# L298N_Motor_Driver.net
KiCad netlist of a schematic drawn in EasyEDA Pro
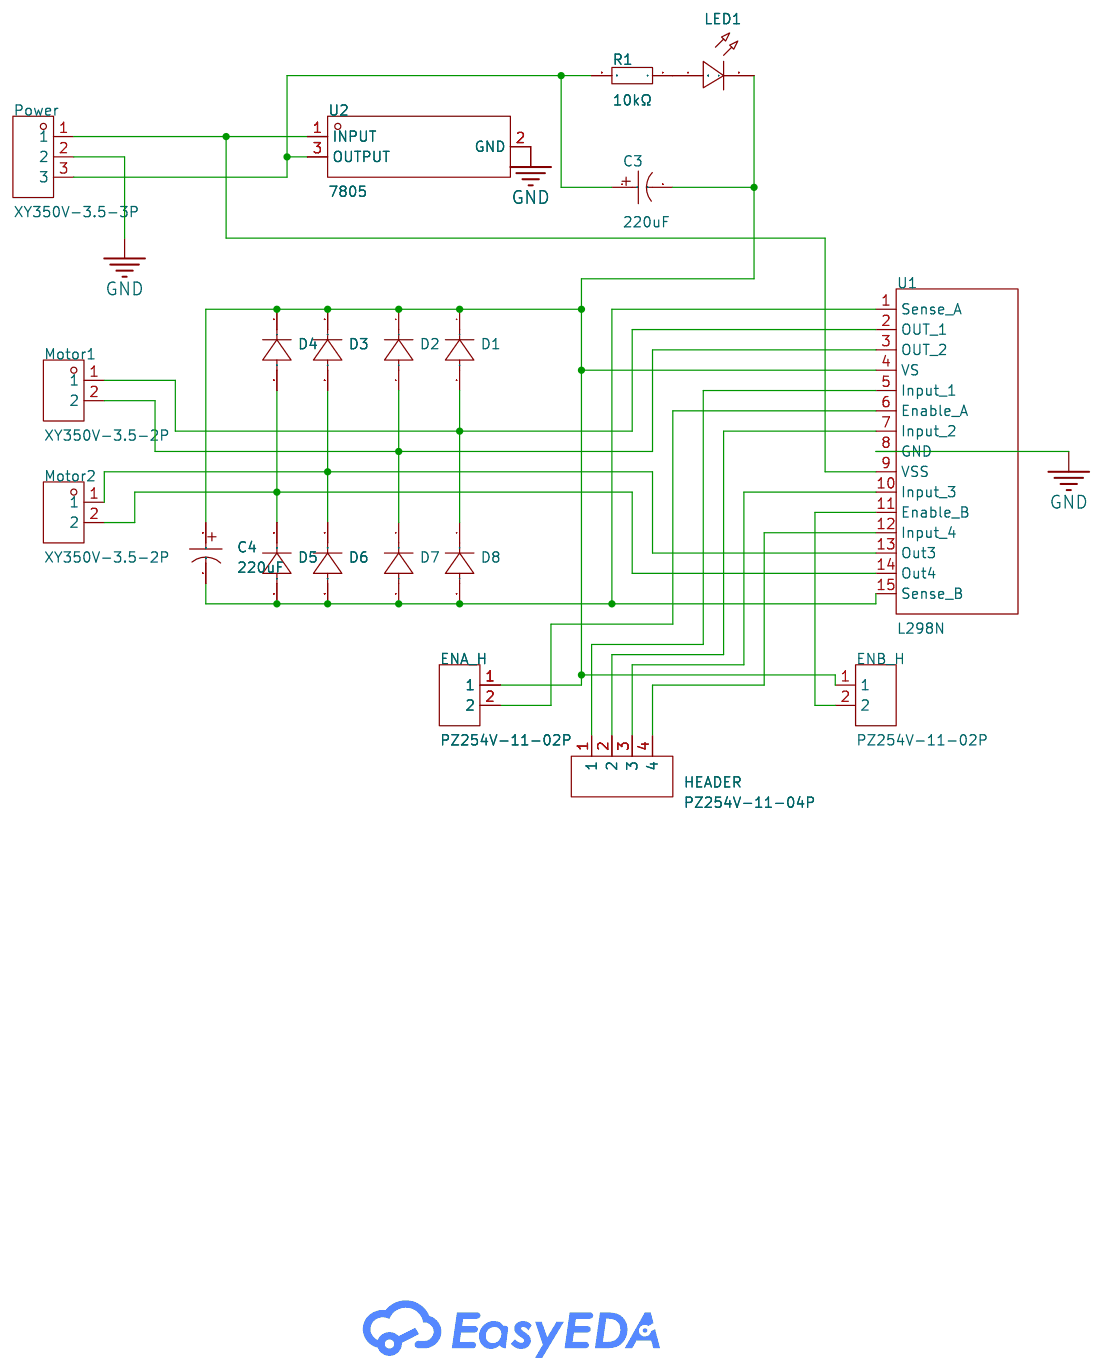
[diagram p0: schematic sheet]

(export (version "E")
  (design (tool "Eeschema 10.0.6"))
  (components
    (comp (ref "C3")
      (value "220uF")
      (footprint "easyedapro:CAP-SMD_BD8.0-L8.3-W8.3-FD")
      (fields (field (name "Manufacturer Part") "RVT1E221M0810") (field (name "Manufacturer") "Chengx(承兴)"))
      (libsource (lib "easyedapro") (part "UT1E221M0810VG"))
    )
    (comp (ref "C4")
      (value "220uF")
      (footprint "easyedapro:CAP-SMD_BD8.0-L8.3-W8.3-FD")
      (fields (field (name "Manufacturer Part") "RVT1E221M0810") (field (name "Manufacturer") "Chengx(承兴)"))
      (libsource (lib "easyedapro") (part "UT1E221M0810VG"))
    )
    (comp (ref "D1")
      (value "~")
      (footprint "easyedapro:DO-41_BD2.4-L4.7-P8.70-D0.9-RD")
      (libsource (lib "easyedapro") (part "D_1N4007"))
    )
    (comp (ref "D2")
      (value "~")
      (footprint "easyedapro:DO-41_BD2.4-L4.7-P8.70-D0.9-RD")
      (libsource (lib "easyedapro") (part "D_1N4007"))
    )
    (comp (ref "D3")
      (value "~")
      (footprint "easyedapro:DO-41_BD2.4-L4.7-P8.70-D0.9-RD")
      (libsource (lib "easyedapro") (part "D_1N4007"))
    )
    (comp (ref "D4")
      (value "~")
      (footprint "easyedapro:DO-41_BD2.4-L4.7-P8.70-D0.9-RD")
      (libsource (lib "easyedapro") (part "D_1N4007"))
    )
    (comp (ref "D5")
      (value "~")
      (footprint "easyedapro:DO-41_BD2.4-L4.7-P8.70-D0.9-RD")
      (libsource (lib "easyedapro") (part "D_1N4007"))
    )
    (comp (ref "D6")
      (value "~")
      (footprint "easyedapro:DO-41_BD2.4-L4.7-P8.70-D0.9-RD")
      (libsource (lib "easyedapro") (part "D_1N4007"))
    )
    (comp (ref "D7")
      (value "~")
      (footprint "easyedapro:DO-41_BD2.4-L4.7-P8.70-D0.9-RD")
      (libsource (lib "easyedapro") (part "D_1N4007"))
    )
    (comp (ref "D8")
      (value "~")
      (footprint "easyedapro:DO-41_BD2.4-L4.7-P8.70-D0.9-RD")
      (libsource (lib "easyedapro") (part "D_1N4007"))
    )
    (comp (ref "ENA_H")
      (value "PZ254V-11-02P")
      (footprint "easyedapro:HDR-TH_2P-P2.54-V-M")
      (fields (field (name "Manufacturer") "XFCN(兴飞)"))
      (libsource (lib "easyedapro") (part "PZ254V-11-02P"))
    )
    (comp (ref "ENB_H")
      (value "PZ254V-11-02P")
      (footprint "easyedapro:HDR-TH_2P-P2.54-V-M")
      (fields (field (name "Manufacturer") "XFCN(兴飞)"))
      (libsource (lib "easyedapro") (part "PZ254V-11-02P"))
    )
    (comp (ref "HEADER")
      (value "PZ254V-11-04P")
      (footprint "easyedapro:HDR-TH_4P-P2.54-V-M")
      (fields (field (name "Manufacturer") "XFCN(兴飞)"))
      (libsource (lib "easyedapro") (part "PZ254V-11-04P"))
    )
    (comp (ref "LED1")
      (value "~")
      (footprint "easyedapro:LED-TH_BD3.0-P2.54-FD")
      (libsource (lib "easyedapro") (part "LED_TH-R"))
    )
    (comp (ref "Motor1")
      (value "XY350V-3.5-2P")
      (footprint "easyedapro:CONN-TH_XY350V-3.5-2P")
      (fields (field (name "Manufacturer") "XINLAIYA(新莱亚)"))
      (libsource (lib "easyedapro") (part "XY350V-3.5-2P"))
    )
    (comp (ref "Motor2")
      (value "XY350V-3.5-2P")
      (footprint "easyedapro:CONN-TH_XY350V-3.5-2P")
      (fields (field (name "Manufacturer") "XINLAIYA(新莱亚)"))
      (libsource (lib "easyedapro") (part "XY350V-3.5-2P"))
    )
    (comp (ref "Power")
      (value "XY350V-3.5-3P")
      (footprint "easyedapro:CONN-TH_XY350V-3.5-3P")
      (fields (field (name "Manufacturer") "XINLAIYA(新莱亚)"))
      (libsource (lib "easyedapro") (part "XY350V-3.5-3P"))
    )
    (comp (ref "R1")
      (value "10kΩ")
      (footprint "easyedapro:RES-TH_BD1.8-L3.2-P7.20-D0.4")
      (libsource (lib "easyedapro") (part "Res"))
    )
    (comp (ref "U1")
      (value "L298N")
      (footprint "easyedapro:MULTIWATT-15_L19.6-W5.0-P1.27-L")
      (fields (field (name "Manufacturer") "HGSEMI(华冠)"))
      (libsource (lib "easyedapro") (part "L298N"))
    )
    (comp (ref "U2")
      (value "7805")
      (footprint "easyedapro:TO-252-2_L6.6-W6.1-P4.57-LS9.9-BR-CW")
      (fields (field (name "Manufacturer") "YFW(佑风微)"))
      (libsource (lib "easyedapro") (part "7805_C19626525"))
    )
  )
  (nets
    (net (code "1") (name "GND") (class "Default")
      (node (ref "Power") (pin "2") (pinfunction "2_2") (pintype "unspecified"))
      (node (ref "U1") (pin "8") (pinfunction "GND_8") (pintype "unspecified"))
      (node (ref "U2") (pin "2") (pinfunction "GND_2") (pintype "unspecified"))
    )
    (net (code "2") (name "Net-(D1-A)") (class "Default")
      (node (ref "D1") (pin "2") (pinfunction "A_2") (pintype "input"))
      (node (ref "D8") (pin "1") (pinfunction "K_1") (pintype "input"))
      (node (ref "Motor1") (pin "1") (pinfunction "1_1") (pintype "unspecified"))
      (node (ref "U1") (pin "2") (pinfunction "OUT_1_2") (pintype "unspecified"))
    )
    (net (code "3") (name "Net-(D1-K)") (class "Default")
      (node (ref "C3") (pin "2") (pinfunction "2_2") (pintype "input"))
      (node (ref "C4") (pin "1") (pinfunction "1_1") (pintype "input"))
      (node (ref "D1") (pin "1") (pinfunction "K_1") (pintype "input"))
      (node (ref "D2") (pin "1") (pinfunction "K_1") (pintype "input"))
      (node (ref "D3") (pin "1") (pinfunction "K_1") (pintype "input"))
      (node (ref "D4") (pin "1") (pinfunction "K_1") (pintype "input"))
      (node (ref "ENA_H") (pin "1") (pinfunction "1_1") (pintype "unspecified"))
      (node (ref "ENB_H") (pin "1") (pinfunction "1_1") (pintype "unspecified"))
      (node (ref "LED1") (pin "2") (pinfunction "A_2") (pintype "input"))
      (node (ref "U1") (pin "4") (pinfunction "VS_4") (pintype "unspecified"))
    )
    (net (code "4") (name "Net-(D2-A)") (class "Default")
      (node (ref "D2") (pin "2") (pinfunction "A_2") (pintype "input"))
      (node (ref "D7") (pin "1") (pinfunction "K_1") (pintype "input"))
      (node (ref "Motor1") (pin "2") (pinfunction "2_2") (pintype "unspecified"))
      (node (ref "U1") (pin "3") (pinfunction "OUT_2_3") (pintype "unspecified"))
    )
    (net (code "5") (name "Net-(D3-A)") (class "Default")
      (node (ref "D3") (pin "2") (pinfunction "A_2") (pintype "input"))
      (node (ref "D6") (pin "1") (pinfunction "K_1") (pintype "input"))
      (node (ref "Motor2") (pin "1") (pinfunction "1_1") (pintype "unspecified"))
      (node (ref "U1") (pin "13") (pinfunction "Out3_13") (pintype "unspecified"))
    )
    (net (code "6") (name "Net-(D4-A)") (class "Default")
      (node (ref "D4") (pin "2") (pinfunction "A_2") (pintype "input"))
      (node (ref "D5") (pin "1") (pinfunction "K_1") (pintype "input"))
      (node (ref "Motor2") (pin "2") (pinfunction "2_2") (pintype "unspecified"))
      (node (ref "U1") (pin "14") (pinfunction "Out4_14") (pintype "unspecified"))
    )
    (net (code "7") (name "Net-(D5-A)") (class "Default")
      (node (ref "C4") (pin "2") (pinfunction "2_2") (pintype "input"))
      (node (ref "D5") (pin "2") (pinfunction "A_2") (pintype "input"))
      (node (ref "D6") (pin "2") (pinfunction "A_2") (pintype "input"))
      (node (ref "D7") (pin "2") (pinfunction "A_2") (pintype "input"))
      (node (ref "D8") (pin "2") (pinfunction "A_2") (pintype "input"))
      (node (ref "U1") (pin "1") (pinfunction "Sense_A_1") (pintype "unspecified"))
      (node (ref "U1") (pin "15") (pinfunction "Sense_B_15") (pintype "unspecified"))
    )
    (net (code "8") (name "Net-(LED1-C)") (class "Default")
      (node (ref "LED1") (pin "1") (pinfunction "C_1") (pintype "input"))
      (node (ref "R1") (pin "1") (pinfunction "1_1") (pintype "input"))
    )
    (net (code "9") (name "Net-(U1-Enable_A)") (class "Default")
      (node (ref "ENA_H") (pin "2") (pinfunction "2_2") (pintype "unspecified"))
      (node (ref "U1") (pin "6") (pinfunction "Enable_A_6") (pintype "unspecified"))
    )
    (net (code "10") (name "Net-(U1-Enable_B)") (class "Default")
      (node (ref "ENB_H") (pin "2") (pinfunction "2_2") (pintype "unspecified"))
      (node (ref "U1") (pin "11") (pinfunction "Enable_B_11") (pintype "unspecified"))
    )
    (net (code "11") (name "Net-(U1-Input_1)") (class "Default")
      (node (ref "HEADER") (pin "1") (pinfunction "1_1") (pintype "unspecified"))
      (node (ref "U1") (pin "5") (pinfunction "Input_1_5") (pintype "unspecified"))
    )
    (net (code "12") (name "Net-(U1-Input_2)") (class "Default")
      (node (ref "HEADER") (pin "2") (pinfunction "2_2") (pintype "unspecified"))
      (node (ref "U1") (pin "7") (pinfunction "Input_2_7") (pintype "unspecified"))
    )
    (net (code "13") (name "Net-(U1-Input_3)") (class "Default")
      (node (ref "HEADER") (pin "3") (pinfunction "3_3") (pintype "unspecified"))
      (node (ref "U1") (pin "10") (pinfunction "Input_3_10") (pintype "unspecified"))
    )
    (net (code "14") (name "Net-(U1-Input_4)") (class "Default")
      (node (ref "HEADER") (pin "4") (pinfunction "4_4") (pintype "unspecified"))
      (node (ref "U1") (pin "12") (pinfunction "Input_4_12") (pintype "unspecified"))
    )
    (net (code "15") (name "Net-(U1-VSS)") (class "Default")
      (node (ref "Power") (pin "1") (pinfunction "1_1") (pintype "unspecified"))
      (node (ref "U1") (pin "9") (pinfunction "VSS_9") (pintype "unspecified"))
      (node (ref "U2") (pin "1") (pinfunction "INPUT_1") (pintype "unspecified"))
    )
    (net (code "16") (name "Net-(U2-OUTPUT)") (class "Default")
      (node (ref "C3") (pin "1") (pinfunction "1_1") (pintype "input"))
      (node (ref "Power") (pin "3") (pinfunction "3_3") (pintype "unspecified"))
      (node (ref "R1") (pin "2") (pinfunction "2_2") (pintype "input"))
      (node (ref "U2") (pin "3") (pinfunction "OUTPUT_3") (pintype "unspecified"))
    )
  )
)
